# nRF24_Arduino_adapter.net
KiCad netlist of a schematic drawn in EAGLE
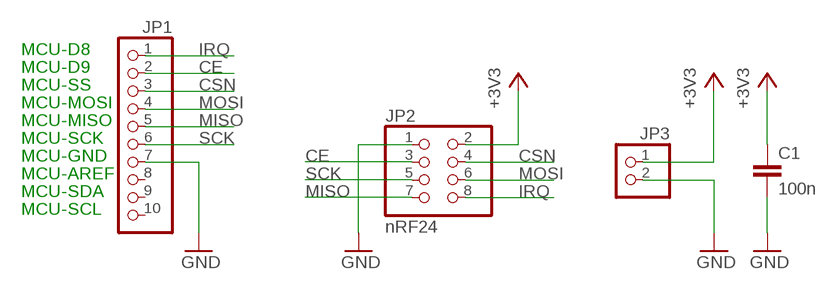
[diagram p0: schematic, sheet 1]

(export (version "E")
  (design (tool "Eeschema 10.0.6"))
  (components
    (comp (ref "C1")
      (value "100n")
      (footprint "eagle-import:C7.5B3")
      (libsource (lib "eagle-import") (part "C7.5/3"))
    )
    (comp (ref "JP1")
      (value "PINHD-1X10")
      (footprint "eagle-import:1X10")
      (libsource (lib "eagle-import") (part "PINHD-1X10"))
    )
    (comp (ref "JP2")
      (value "nRF24")
      (footprint "eagle-import:2X04")
      (libsource (lib "eagle-import") (part "PINHD-2X4"))
    )
    (comp (ref "JP3")
      (value "PINHD-1X2")
      (footprint "eagle-import:1X02")
      (libsource (lib "eagle-import") (part "PINHD-1X2"))
    )
  )
  (nets
    (net (code "1") (name "+3V3") (class "Default")
      (node (ref "C1") (pin "1") (pinfunction "1_1") (pintype "passive"))
      (node (ref "JP2") (pin "2") (pinfunction "2_2") (pintype "passive"))
      (node (ref "JP3") (pin "1") (pinfunction "1_1") (pintype "passive"))
    )
    (net (code "2") (name "/CE") (class "Default")
      (node (ref "JP1") (pin "2") (pinfunction "2_2") (pintype "passive"))
      (node (ref "JP2") (pin "3") (pinfunction "3_3") (pintype "passive"))
    )
    (net (code "3") (name "/CSN") (class "Default")
      (node (ref "JP1") (pin "3") (pinfunction "3_3") (pintype "passive"))
      (node (ref "JP2") (pin "4") (pinfunction "4_4") (pintype "passive"))
    )
    (net (code "4") (name "/IRQ") (class "Default")
      (node (ref "JP1") (pin "1") (pinfunction "1_1") (pintype "passive"))
      (node (ref "JP2") (pin "8") (pinfunction "8_8") (pintype "passive"))
    )
    (net (code "5") (name "/MISO") (class "Default")
      (node (ref "JP1") (pin "5") (pinfunction "5_5") (pintype "passive"))
      (node (ref "JP2") (pin "7") (pinfunction "7_7") (pintype "passive"))
    )
    (net (code "6") (name "/MOSI") (class "Default")
      (node (ref "JP1") (pin "4") (pinfunction "4_4") (pintype "passive"))
      (node (ref "JP2") (pin "6") (pinfunction "6_6") (pintype "passive"))
    )
    (net (code "7") (name "/SCK") (class "Default")
      (node (ref "JP1") (pin "6") (pinfunction "6_6") (pintype "passive"))
      (node (ref "JP2") (pin "5") (pinfunction "5_5") (pintype "passive"))
    )
    (net (code "8") (name "GND") (class "Default")
      (node (ref "C1") (pin "2") (pinfunction "2_2") (pintype "passive"))
      (node (ref "JP1") (pin "7") (pinfunction "7_7") (pintype "passive"))
      (node (ref "JP2") (pin "1") (pinfunction "1_1") (pintype "passive"))
      (node (ref "JP3") (pin "2") (pinfunction "2_2") (pintype "passive"))
    )
    (net (code "9") (name "unconnected-(JP1-Pad8)") (class "Default")
      (node (ref "JP1") (pin "8") (pinfunction "8_8") (pintype "passive"))
    )
    (net (code "10") (name "unconnected-(JP1-Pad9)") (class "Default")
      (node (ref "JP1") (pin "9") (pinfunction "9_9") (pintype "passive"))
    )
    (net (code "11") (name "unconnected-(JP1-Pad10)") (class "Default")
      (node (ref "JP1") (pin "10") (pinfunction "10_10") (pintype "passive"))
    )
  )
)
